# impulse.net
KiCad netlist of a schematic drawn in EAGLE
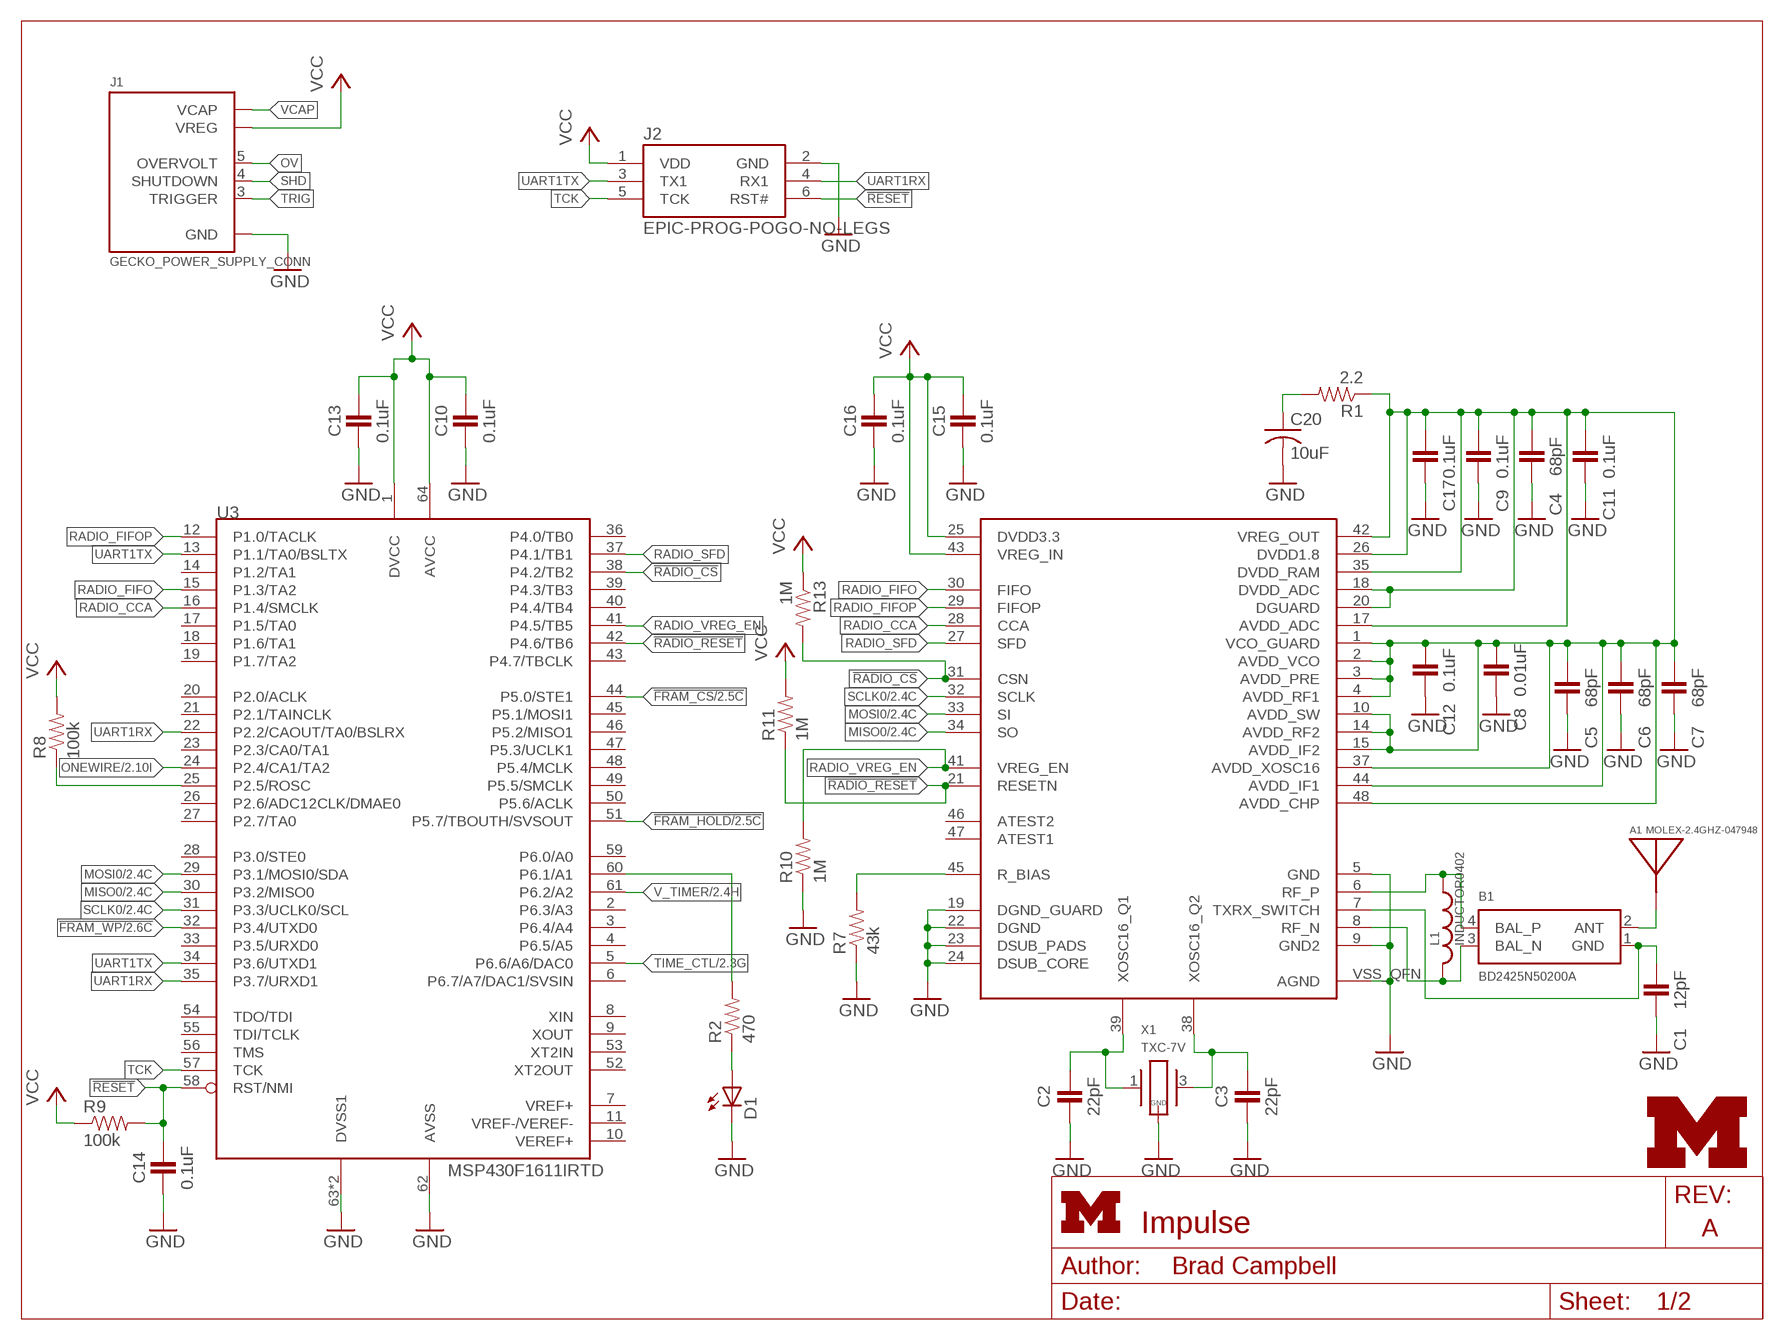
[diagram p0: schematic, sheet 1]
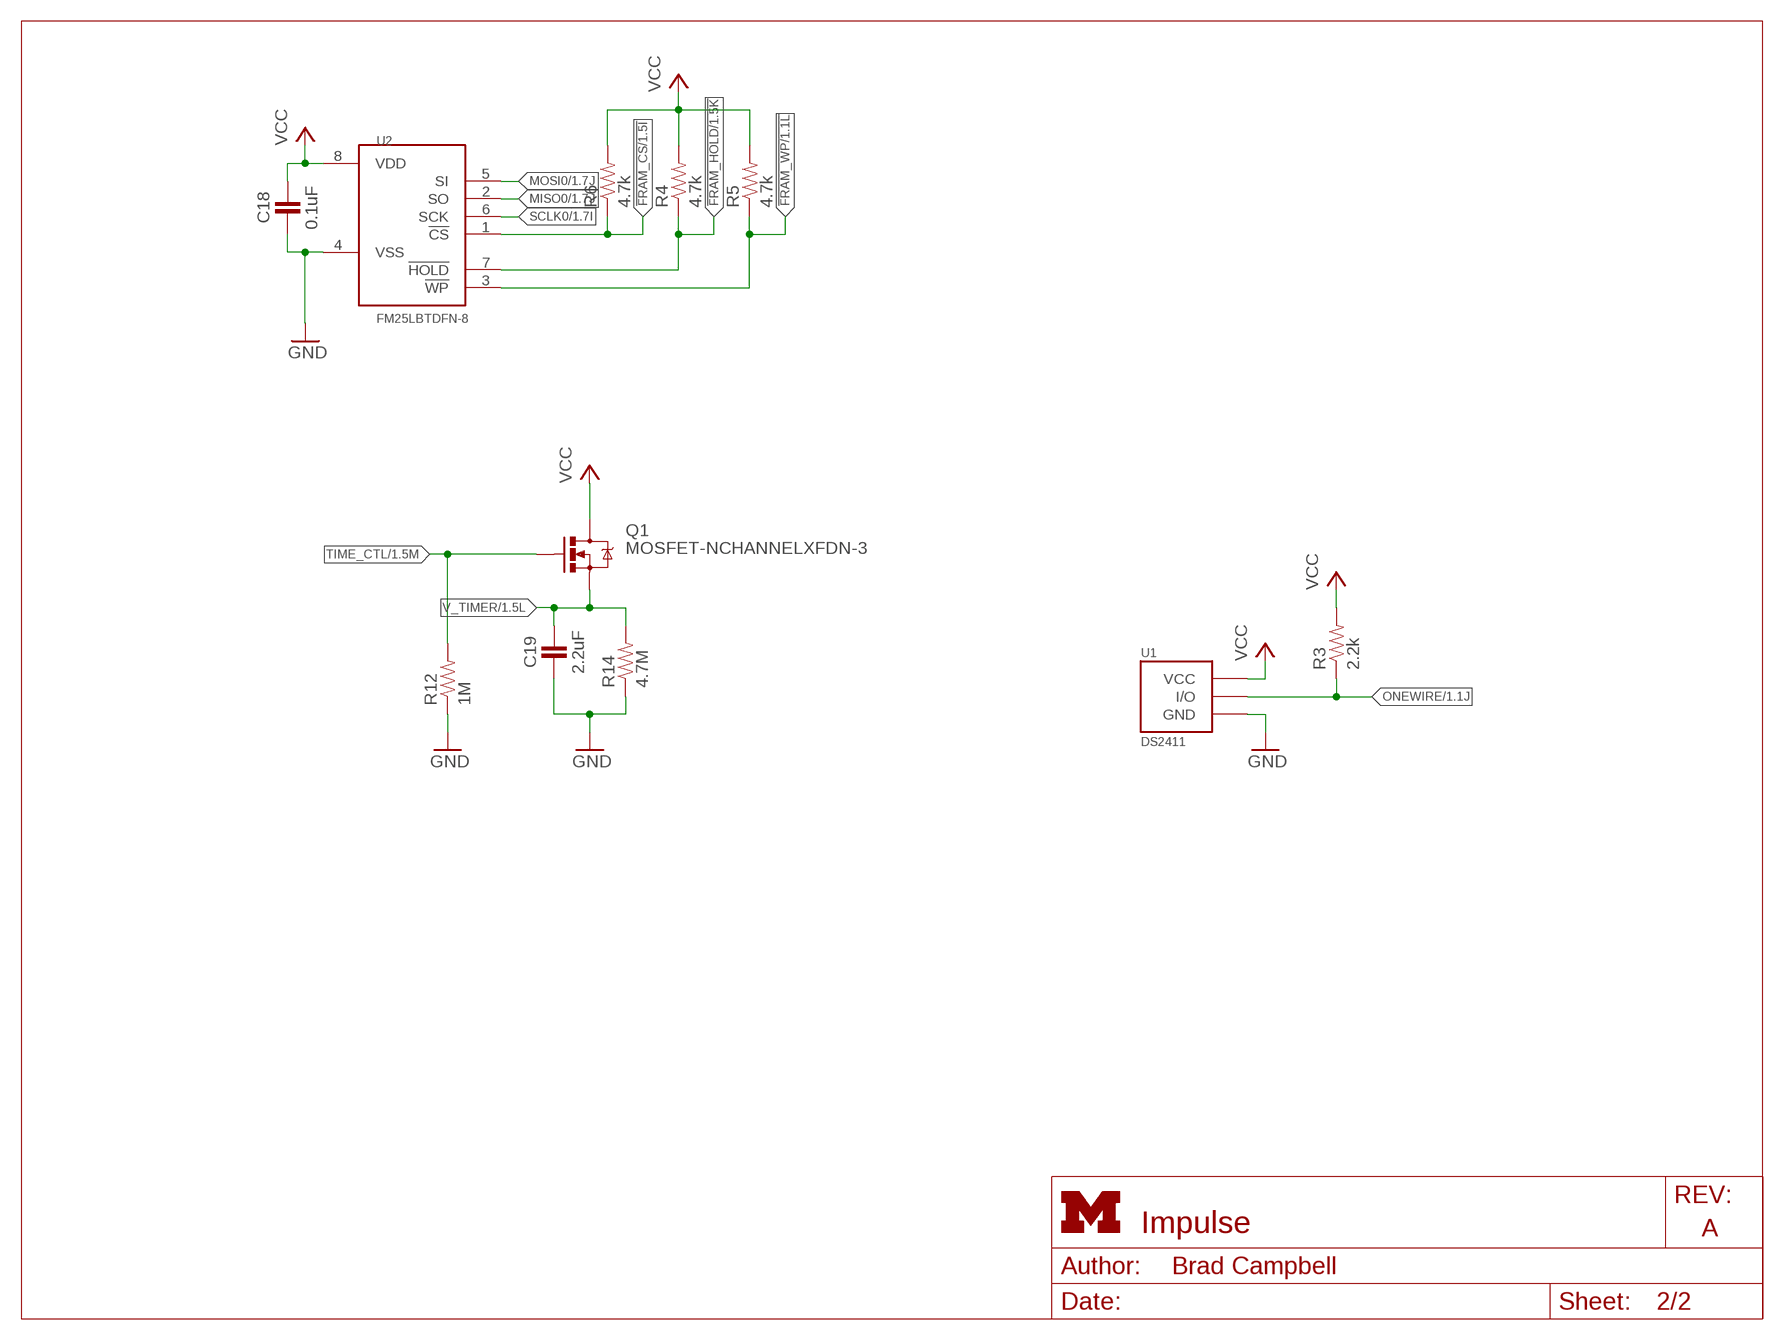
[diagram p1: schematic, sheet 2]

(export (version "E")
  (design (tool "Eeschema 10.0.6"))
  (components
    (comp (ref "A1")
      (value "MOLEX-2.4GHZ-047948")
      (footprint "eagle-import:MOLEX-47948-ANTENNA")
      (libsource (lib "eagle-import") (part "MOLEX-2.4GHZ-047948"))
    )
    (comp (ref "B1")
      (value "BD2425N50200A")
      (footprint "eagle-import:BD2425N50200A")
      (libsource (lib "eagle-import") (part "BD2425N50200A"))
    )
    (comp (ref "C1")
      (value "12pF")
      (footprint "eagle-import:0402_CAP")
      (libsource (lib "eagle-import") (part "CAPACITOR"))
    )
    (comp (ref "C2")
      (value "22pF")
      (footprint "eagle-import:0402_CAP")
      (libsource (lib "eagle-import") (part "CAPACITOR"))
    )
    (comp (ref "C3")
      (value "22pF")
      (footprint "eagle-import:0402_CAP")
      (libsource (lib "eagle-import") (part "CAPACITOR"))
    )
    (comp (ref "C4")
      (value "68pF")
      (footprint "eagle-import:0402_CAP")
      (libsource (lib "eagle-import") (part "CAPACITOR"))
    )
    (comp (ref "C5")
      (value "68pF")
      (footprint "eagle-import:0402_CAP")
      (libsource (lib "eagle-import") (part "CAPACITOR"))
    )
    (comp (ref "C6")
      (value "68pF")
      (footprint "eagle-import:0402_CAP")
      (libsource (lib "eagle-import") (part "CAPACITOR"))
    )
    (comp (ref "C7")
      (value "68pF")
      (footprint "eagle-import:0402_CAP")
      (libsource (lib "eagle-import") (part "CAPACITOR"))
    )
    (comp (ref "C8")
      (value "0.01uF")
      (footprint "eagle-import:0402_CAP")
      (libsource (lib "eagle-import") (part "CAPACITOR"))
    )
    (comp (ref "C9")
      (value "0.1uF")
      (footprint "eagle-import:0402_CAP")
      (libsource (lib "eagle-import") (part "CAPACITOR"))
    )
    (comp (ref "C10")
      (value "0.1uF")
      (footprint "eagle-import:0402_CAP")
      (libsource (lib "eagle-import") (part "CAPACITOR"))
    )
    (comp (ref "C11")
      (value "0.1uF")
      (footprint "eagle-import:0402_CAP")
      (libsource (lib "eagle-import") (part "CAPACITOR"))
    )
    (comp (ref "C12")
      (value "0.1uF")
      (footprint "eagle-import:0402_CAP")
      (libsource (lib "eagle-import") (part "CAPACITOR"))
    )
    (comp (ref "C13")
      (value "0.1uF")
      (footprint "eagle-import:0402_CAP")
      (libsource (lib "eagle-import") (part "CAPACITOR"))
    )
    (comp (ref "C14")
      (value "0.1uF")
      (footprint "eagle-import:0402_CAP")
      (libsource (lib "eagle-import") (part "CAPACITOR"))
    )
    (comp (ref "C15")
      (value "0.1uF")
      (footprint "eagle-import:0402_CAP")
      (libsource (lib "eagle-import") (part "CAPACITOR"))
    )
    (comp (ref "C16")
      (value "0.1uF")
      (footprint "eagle-import:0402_CAP")
      (libsource (lib "eagle-import") (part "CAPACITOR"))
    )
    (comp (ref "C17")
      (value "0.1uF")
      (footprint "eagle-import:0402_CAP")
      (libsource (lib "eagle-import") (part "CAPACITOR"))
    )
    (comp (ref "C20")
      (value "10uF")
      (footprint "eagle-import:C0805")
      (libsource (lib "eagle-import") (part "C-USC0805"))
    )
    (comp (ref "D1")
      (value "LED0603")
      (footprint "eagle-import:LED-0603")
      (libsource (lib "eagle-import") (part "LED0603"))
    )
    (comp (ref "J1")
      (value "GECKO_POWER_SUPPLY_CONN")
      (footprint "eagle-import:HEADER1X6_0.05IN")
      (libsource (lib "eagle-import") (part "GECKO_POWER_SUPPLY_CONN"))
    )
    (comp (ref "J2")
      (value "EPIC-PROG-POGO-NO-LEGS")
      (footprint "eagle-import:TC2030-IDC-NL")
      (libsource (lib "eagle-import") (part "EPIC-PROG-POGO-NO-LEGS"))
    )
    (comp (ref "L1")
      (value "INDUCTOR0402")
      (footprint "eagle-import:0402_CAP")
      (libsource (lib "eagle-import") (part "INDUCTOR0402"))
    )
    (comp (ref "R1")
      (value "2.2")
      (footprint "eagle-import:0402_RES")
      (libsource (lib "eagle-import") (part "RESISTOR"))
    )
    (comp (ref "R2")
      (value "470")
      (footprint "eagle-import:0402_RES")
      (libsource (lib "eagle-import") (part "RESISTOR"))
    )
    (comp (ref "R7")
      (value "43k")
      (footprint "eagle-import:0402_RES")
      (libsource (lib "eagle-import") (part "RESISTOR"))
    )
    (comp (ref "R8")
      (value "100k")
      (footprint "eagle-import:0402_RES")
      (libsource (lib "eagle-import") (part "RESISTOR"))
    )
    (comp (ref "R9")
      (value "100k")
      (footprint "eagle-import:0402_RES")
      (libsource (lib "eagle-import") (part "RESISTOR"))
    )
    (comp (ref "R10")
      (value "1M")
      (footprint "eagle-import:0402_RES")
      (libsource (lib "eagle-import") (part "RESISTOR"))
    )
    (comp (ref "R11")
      (value "1M")
      (footprint "eagle-import:0402_RES")
      (libsource (lib "eagle-import") (part "RESISTOR"))
    )
    (comp (ref "R13")
      (value "1M")
      (footprint "eagle-import:0402_RES")
      (libsource (lib "eagle-import") (part "RESISTOR"))
    )
    (comp (ref "U$1")
      (value "UMICH_SOLID_SMALL")
      (footprint "eagle-import:UMICH_SOLID_75MIL")
      (libsource (lib "eagle-import") (part "UMICH_SOLID_SMALL"))
    )
    (comp (ref "U3")
      (value "MSP430F1611IRTD")
      (footprint "eagle-import:S-PVQFN-N64")
      (libsource (lib "eagle-import") (part "MSP430F1611IRTD"))
    )
    (comp (ref "U4")
      (value "CC2420RGZ")
      (footprint "eagle-import:S-PVQFN-N48")
      (libsource (lib "eagle-import") (part "CC2420RGZ"))
    )
    (comp (ref "X1")
      (value "TXC-7V")
      (footprint "eagle-import:TXC-7V")
      (libsource (lib "eagle-import") (part "TXC-7V"))
    )
    (comp (ref "C18")
      (value "0.1uF")
      (footprint "eagle-import:0402_CAP")
      (libsource (lib "eagle-import") (part "CAPACITOR"))
    )
    (comp (ref "C19")
      (value "2.2uF")
      (footprint "eagle-import:0402_CAP")
      (libsource (lib "eagle-import") (part "CAPACITOR"))
    )
    (comp (ref "Q1")
      (value "MOSFET-NCHANNELXFDN-3")
      (footprint "eagle-import:XFDFN-3")
      (libsource (lib "eagle-import") (part "MOSFET-NCHANNELXFDN-3"))
    )
    (comp (ref "R3")
      (value "2.2k")
      (footprint "eagle-import:0402_RES")
      (libsource (lib "eagle-import") (part "RESISTOR"))
    )
    (comp (ref "R4")
      (value "4.7k")
      (footprint "eagle-import:0402_RES")
      (libsource (lib "eagle-import") (part "RESISTOR"))
    )
    (comp (ref "R5")
      (value "4.7k")
      (footprint "eagle-import:0402_RES")
      (libsource (lib "eagle-import") (part "RESISTOR"))
    )
    (comp (ref "R6")
      (value "4.7k")
      (footprint "eagle-import:0402_RES")
      (libsource (lib "eagle-import") (part "RESISTOR"))
    )
    (comp (ref "R12")
      (value "1M")
      (footprint "eagle-import:0402_RES")
      (libsource (lib "eagle-import") (part "RESISTOR"))
    )
    (comp (ref "R14")
      (value "4.7M")
      (footprint "eagle-import:0402_RES")
      (libsource (lib "eagle-import") (part "RESISTOR"))
    )
    (comp (ref "U1")
      (value "DS2411")
      (footprint "eagle-import:SOT-23")
      (libsource (lib "eagle-import") (part "DS2411"))
    )
    (comp (ref "U2")
      (value "FM25LBTDFN-8")
      (footprint "eagle-import:TDFN-8")
      (libsource (lib "eagle-import") (part "FM25LBTDFN-8"))
    )
  )
  (nets
    (net (code "1") (name "GND") (class "Default")
      (node (ref "C1") (pin "2") (pinfunction "2_2") (pintype "bidirectional"))
      (node (ref "C10") (pin "2") (pinfunction "2_2") (pintype "bidirectional"))
      (node (ref "C11") (pin "2") (pinfunction "2_2") (pintype "bidirectional"))
      (node (ref "C12") (pin "2") (pinfunction "2_2") (pintype "bidirectional"))
      (node (ref "C13") (pin "2") (pinfunction "2_2") (pintype "bidirectional"))
      (node (ref "C14") (pin "2") (pinfunction "2_2") (pintype "bidirectional"))
      (node (ref "C15") (pin "2") (pinfunction "2_2") (pintype "bidirectional"))
      (node (ref "C16") (pin "2") (pinfunction "2_2") (pintype "bidirectional"))
      (node (ref "C17") (pin "2") (pinfunction "2_2") (pintype "bidirectional"))
      (node (ref "C18") (pin "2") (pinfunction "2_2") (pintype "bidirectional"))
      (node (ref "C19") (pin "2") (pinfunction "2_2") (pintype "bidirectional"))
      (node (ref "C2") (pin "2") (pinfunction "2_2") (pintype "bidirectional"))
      (node (ref "C20") (pin "2") (pinfunction "2_2") (pintype "passive"))
      (node (ref "C3") (pin "2") (pinfunction "2_2") (pintype "bidirectional"))
      (node (ref "C4") (pin "2") (pinfunction "2_2") (pintype "bidirectional"))
      (node (ref "C5") (pin "2") (pinfunction "2_2") (pintype "bidirectional"))
      (node (ref "C6") (pin "2") (pinfunction "2_2") (pintype "bidirectional"))
      (node (ref "C7") (pin "2") (pinfunction "2_2") (pintype "bidirectional"))
      (node (ref "C8") (pin "2") (pinfunction "2_2") (pintype "bidirectional"))
      (node (ref "C9") (pin "2") (pinfunction "2_2") (pintype "bidirectional"))
      (node (ref "D1") (pin "C") (pinfunction "C_C") (pintype "passive"))
      (node (ref "J1") (pin "1") (pinfunction "GND_1") (pintype "bidirectional"))
      (node (ref "J2") (pin "2") (pinfunction "GND_2") (pintype "bidirectional"))
      (node (ref "R10") (pin "1") (pinfunction "1_1") (pintype "passive"))
      (node (ref "R12") (pin "1") (pinfunction "1_1") (pintype "passive"))
      (node (ref "R14") (pin "1") (pinfunction "1_1") (pintype "passive"))
      (node (ref "R7") (pin "1") (pinfunction "1_1") (pintype "passive"))
      (node (ref "U1") (pin "3") (pinfunction "GND_3") (pintype "bidirectional"))
      (node (ref "U2") (pin "4") (pinfunction "VSS_4") (pintype "bidirectional"))
      (node (ref "U3") (pin "62") (pinfunction "AVSS_62") (pintype "power_in"))
      (node (ref "U3") (pin "63") (pinfunction "DVSS1_63") (pintype "power_in"))
      (node (ref "U3") (pin "GND") (pinfunction "DVSS1_GND") (pintype "power_in"))
      (node (ref "U4") (pin "19") (pinfunction "DGND_GUARD_19") (pintype "bidirectional"))
      (node (ref "U4") (pin "22") (pinfunction "DGND_22") (pintype "bidirectional"))
      (node (ref "U4") (pin "23") (pinfunction "DSUB_PADS_23") (pintype "bidirectional"))
      (node (ref "U4") (pin "24") (pinfunction "DSUB_CORE_24") (pintype "bidirectional"))
      (node (ref "U4") (pin "5") (pinfunction "GND_5") (pintype "bidirectional"))
      (node (ref "U4") (pin "9") (pinfunction "GND2_9") (pintype "bidirectional"))
      (node (ref "U4") (pin "VSS_QFN") (pinfunction "AGND_VSS_QFN") (pintype "bidirectional"))
      (node (ref "X1") (pin "2") (pinfunction "GND_2") (pintype "bidirectional"))
      (node (ref "X1") (pin "4") (pinfunction "GND_4") (pintype "bidirectional"))
    )
    (net (code "2") (name "MISO0") (class "Default")
      (node (ref "U2") (pin "2") (pinfunction "SO_2") (pintype "bidirectional"))
      (node (ref "U3") (pin "30") (pinfunction "P3.2/MISO0_30") (pintype "bidirectional"))
      (node (ref "U4") (pin "34") (pinfunction "SO_34") (pintype "bidirectional"))
    )
    (net (code "3") (name "MOSI0") (class "Default")
      (node (ref "U2") (pin "5") (pinfunction "SI_5") (pintype "bidirectional"))
      (node (ref "U3") (pin "29") (pinfunction "P3.1/MOSI0/SDA_29") (pintype "bidirectional"))
      (node (ref "U4") (pin "33") (pinfunction "SI_33") (pintype "bidirectional"))
    )
    (net (code "4") (name "Net-(A1-ANTENNA)") (class "Default")
      (node (ref "A1") (pin "1") (pinfunction "ANTENNA_1") (pintype "bidirectional"))
      (node (ref "B1") (pin "2") (pinfunction "ANT_2") (pintype "bidirectional"))
    )
    (net (code "5") (name "Net-(B1-BAL_N)") (class "Default")
      (node (ref "B1") (pin "3") (pinfunction "BAL_N_3") (pintype "bidirectional"))
      (node (ref "L1") (pin "2") (pinfunction "P$2_2") (pintype "bidirectional"))
      (node (ref "U4") (pin "8") (pinfunction "RF_N_8") (pintype "bidirectional"))
    )
    (net (code "6") (name "Net-(B1-BAL_P)") (class "Default")
      (node (ref "B1") (pin "4") (pinfunction "BAL_P_4") (pintype "bidirectional"))
      (node (ref "L1") (pin "1") (pinfunction "1_1") (pintype "bidirectional"))
      (node (ref "U4") (pin "6") (pinfunction "RF_P_6") (pintype "bidirectional"))
    )
    (net (code "7") (name "Net-(B1-GND)") (class "Default")
      (node (ref "B1") (pin "1") (pinfunction "GND_1") (pintype "bidirectional"))
      (node (ref "C1") (pin "1") (pinfunction "1_1") (pintype "bidirectional"))
      (node (ref "U4") (pin "7") (pinfunction "TXRX_SWITCH_7") (pintype "bidirectional"))
    )
    (net (code "8") (name "Net-(C20-Pad1)") (class "Default")
      (node (ref "C20") (pin "1") (pinfunction "1_1") (pintype "passive"))
      (node (ref "R1") (pin "2") (pinfunction "2_2") (pintype "passive"))
    )
    (net (code "9") (name "Net-(D1-PadA)") (class "Default")
      (node (ref "D1") (pin "A") (pinfunction "A_A") (pintype "passive"))
      (node (ref "R2") (pin "1") (pinfunction "1_1") (pintype "passive"))
    )
    (net (code "10") (name "Net-(U3-P2.5{slash}ROSC)") (class "Default")
      (node (ref "R8") (pin "1") (pinfunction "1_1") (pintype "passive"))
      (node (ref "U3") (pin "25") (pinfunction "P2.5/ROSC_25") (pintype "bidirectional"))
    )
    (net (code "11") (name "Net-(U3-P6.1{slash}A1)") (class "Default")
      (node (ref "R2") (pin "2") (pinfunction "2_2") (pintype "passive"))
      (node (ref "U3") (pin "60") (pinfunction "P6.1/A1_60") (pintype "bidirectional"))
    )
    (net (code "12") (name "Net-(U4-AVDD_ADC)") (class "Default")
      (node (ref "C11") (pin "1") (pinfunction "1_1") (pintype "bidirectional"))
      (node (ref "C12") (pin "1") (pinfunction "1_1") (pintype "bidirectional"))
      (node (ref "C17") (pin "1") (pinfunction "1_1") (pintype "bidirectional"))
      (node (ref "C4") (pin "1") (pinfunction "1_1") (pintype "bidirectional"))
      (node (ref "C5") (pin "1") (pinfunction "1_1") (pintype "bidirectional"))
      (node (ref "C6") (pin "1") (pinfunction "1_1") (pintype "bidirectional"))
      (node (ref "C7") (pin "1") (pinfunction "1_1") (pintype "bidirectional"))
      (node (ref "C8") (pin "1") (pinfunction "1_1") (pintype "bidirectional"))
      (node (ref "C9") (pin "1") (pinfunction "1_1") (pintype "bidirectional"))
      (node (ref "R1") (pin "1") (pinfunction "1_1") (pintype "passive"))
      (node (ref "U4") (pin "1") (pinfunction "VCO_GUARD_1") (pintype "bidirectional"))
      (node (ref "U4") (pin "10") (pinfunction "AVDD_SW_10") (pintype "bidirectional"))
      (node (ref "U4") (pin "14") (pinfunction "AVDD_RF2_14") (pintype "bidirectional"))
      (node (ref "U4") (pin "15") (pinfunction "AVDD_IF2_15") (pintype "bidirectional"))
      (node (ref "U4") (pin "17") (pinfunction "AVDD_ADC_17") (pintype "bidirectional"))
      (node (ref "U4") (pin "18") (pinfunction "DVDD_ADC_18") (pintype "bidirectional"))
      (node (ref "U4") (pin "2") (pinfunction "AVDD_VCO_2") (pintype "bidirectional"))
      (node (ref "U4") (pin "20") (pinfunction "DGUARD_20") (pintype "bidirectional"))
      (node (ref "U4") (pin "26") (pinfunction "DVDD1.8_26") (pintype "bidirectional"))
      (node (ref "U4") (pin "3") (pinfunction "AVDD_PRE_3") (pintype "bidirectional"))
      (node (ref "U4") (pin "35") (pinfunction "DVDD_RAM_35") (pintype "bidirectional"))
      (node (ref "U4") (pin "37") (pinfunction "AVDD_XOSC16_37") (pintype "bidirectional"))
      (node (ref "U4") (pin "4") (pinfunction "AVDD_RF1_4") (pintype "bidirectional"))
      (node (ref "U4") (pin "42") (pinfunction "VREG_OUT_42") (pintype "bidirectional"))
      (node (ref "U4") (pin "44") (pinfunction "AVDD_IF1_44") (pintype "bidirectional"))
      (node (ref "U4") (pin "48") (pinfunction "AVDD_CHP_48") (pintype "bidirectional"))
    )
    (net (code "13") (name "Net-(U4-R_BIAS)") (class "Default")
      (node (ref "R7") (pin "2") (pinfunction "2_2") (pintype "passive"))
      (node (ref "U4") (pin "45") (pinfunction "R_BIAS_45") (pintype "bidirectional"))
    )
    (net (code "14") (name "Net-(U4-XOSC16_Q1)") (class "Default")
      (node (ref "C2") (pin "1") (pinfunction "1_1") (pintype "bidirectional"))
      (node (ref "U4") (pin "39") (pinfunction "XOSC16_Q1_39") (pintype "bidirectional"))
      (node (ref "X1") (pin "1") (pinfunction "1_1") (pintype "bidirectional"))
    )
    (net (code "15") (name "Net-(U4-XOSC16_Q2)") (class "Default")
      (node (ref "C3") (pin "1") (pinfunction "1_1") (pintype "bidirectional"))
      (node (ref "U4") (pin "38") (pinfunction "XOSC16_Q2_38") (pintype "bidirectional"))
      (node (ref "X1") (pin "3") (pinfunction "2_3") (pintype "bidirectional"))
    )
    (net (code "16") (name "ONEWIRE") (class "Default")
      (node (ref "R3") (pin "1") (pinfunction "1_1") (pintype "passive"))
      (node (ref "U1") (pin "1") (pinfunction "I/O_1") (pintype "bidirectional"))
      (node (ref "U3") (pin "24") (pinfunction "P2.4/CA1/TA2_24") (pintype "bidirectional"))
    )
    (net (code "17") (name "OV") (class "Default")
      (node (ref "J1") (pin "5") (pinfunction "OVERVOLT_5") (pintype "bidirectional"))
    )
    (net (code "18") (name "RADIO_CCA") (class "Default")
      (node (ref "U3") (pin "16") (pinfunction "P1.4/SMCLK_16") (pintype "bidirectional"))
      (node (ref "U4") (pin "28") (pinfunction "CCA_28") (pintype "bidirectional"))
    )
    (net (code "19") (name "RADIO_FIFO") (class "Default")
      (node (ref "U3") (pin "15") (pinfunction "P1.3/TA2_15") (pintype "bidirectional"))
      (node (ref "U4") (pin "30") (pinfunction "FIFO_30") (pintype "bidirectional"))
    )
    (net (code "20") (name "RADIO_FIFOP") (class "Default")
      (node (ref "U3") (pin "12") (pinfunction "P1.0/TACLK_12") (pintype "bidirectional"))
      (node (ref "U4") (pin "29") (pinfunction "FIFOP_29") (pintype "bidirectional"))
    )
    (net (code "21") (name "RADIO_SFD") (class "Default")
      (node (ref "U3") (pin "37") (pinfunction "P4.1/TB1_37") (pintype "bidirectional"))
      (node (ref "U4") (pin "27") (pinfunction "SFD_27") (pintype "bidirectional"))
    )
    (net (code "22") (name "RADIO_VREG_EN") (class "Default")
      (node (ref "R10") (pin "2") (pinfunction "2_2") (pintype "passive"))
      (node (ref "U3") (pin "41") (pinfunction "P4.5/TB5_41") (pintype "bidirectional"))
      (node (ref "U4") (pin "41") (pinfunction "VREG_EN_41") (pintype "bidirectional"))
    )
    (net (code "23") (name "SCLK0") (class "Default")
      (node (ref "U2") (pin "6") (pinfunction "SCK_6") (pintype "bidirectional"))
      (node (ref "U3") (pin "31") (pinfunction "P3.3/UCLK0/SCL_31") (pintype "bidirectional"))
      (node (ref "U4") (pin "32") (pinfunction "SCLK_32") (pintype "bidirectional"))
    )
    (net (code "24") (name "SHD") (class "Default")
      (node (ref "J1") (pin "4") (pinfunction "SHUTDOWN_4") (pintype "bidirectional"))
    )
    (net (code "25") (name "TCK") (class "Default")
      (node (ref "J2") (pin "5") (pinfunction "TCK_5") (pintype "bidirectional"))
      (node (ref "U3") (pin "57") (pinfunction "TCK_57") (pintype "bidirectional"))
    )
    (net (code "26") (name "TIME_CTL") (class "Default")
      (node (ref "Q1") (pin "G") (pinfunction "G_G") (pintype "passive"))
      (node (ref "R12") (pin "2") (pinfunction "2_2") (pintype "passive"))
      (node (ref "U3") (pin "5") (pinfunction "P6.6/A6/DAC0_5") (pintype "bidirectional"))
    )
    (net (code "27") (name "TRIG") (class "Default")
      (node (ref "J1") (pin "3") (pinfunction "TRIGGER_3") (pintype "bidirectional"))
    )
    (net (code "28") (name "UART1RX") (class "Default")
      (node (ref "J2") (pin "4") (pinfunction "RX1_4") (pintype "bidirectional"))
      (node (ref "U3") (pin "22") (pinfunction "P2.2/CAOUT/TA0/BSLRX_22") (pintype "bidirectional"))
      (node (ref "U3") (pin "35") (pinfunction "P3.7/URXD1_35") (pintype "bidirectional"))
    )
    (net (code "29") (name "UART1TX") (class "Default")
      (node (ref "J2") (pin "3") (pinfunction "TX1_3") (pintype "bidirectional"))
      (node (ref "U3") (pin "13") (pinfunction "P1.1/TA0/BSLTX_13") (pintype "bidirectional"))
      (node (ref "U3") (pin "34") (pinfunction "P3.6/UTXD1_34") (pintype "bidirectional"))
    )
    (net (code "30") (name "VCAP") (class "Default")
      (node (ref "J1") (pin "6") (pinfunction "VCAP_6") (pintype "output"))
    )
    (net (code "31") (name "VCC") (class "Default")
      (node (ref "C10") (pin "1") (pinfunction "1_1") (pintype "bidirectional"))
      (node (ref "C13") (pin "1") (pinfunction "1_1") (pintype "bidirectional"))
      (node (ref "C15") (pin "1") (pinfunction "1_1") (pintype "bidirectional"))
      (node (ref "C16") (pin "1") (pinfunction "1_1") (pintype "bidirectional"))
      (node (ref "C18") (pin "1") (pinfunction "1_1") (pintype "bidirectional"))
      (node (ref "J1") (pin "2") (pinfunction "VREG_2") (pintype "bidirectional"))
      (node (ref "J2") (pin "1") (pinfunction "VDD_1") (pintype "bidirectional"))
      (node (ref "Q1") (pin "D") (pinfunction "D_D") (pintype "passive"))
      (node (ref "R11") (pin "2") (pinfunction "2_2") (pintype "passive"))
      (node (ref "R13") (pin "1") (pinfunction "1_1") (pintype "passive"))
      (node (ref "R3") (pin "2") (pinfunction "2_2") (pintype "passive"))
      (node (ref "R4") (pin "2") (pinfunction "2_2") (pintype "passive"))
      (node (ref "R5") (pin "2") (pinfunction "2_2") (pintype "passive"))
      (node (ref "R6") (pin "2") (pinfunction "2_2") (pintype "passive"))
      (node (ref "R8") (pin "2") (pinfunction "2_2") (pintype "passive"))
      (node (ref "R9") (pin "1") (pinfunction "1_1") (pintype "passive"))
      (node (ref "U1") (pin "2") (pinfunction "VCC_2") (pintype "bidirectional"))
      (node (ref "U2") (pin "8") (pinfunction "VDD_8") (pintype "bidirectional"))
      (node (ref "U3") (pin "1") (pinfunction "DVCC_1") (pintype "power_in"))
      (node (ref "U3") (pin "64") (pinfunction "AVCC_64") (pintype "power_in"))
      (node (ref "U4") (pin "25") (pinfunction "DVDD3.3_25") (pintype "bidirectional"))
      (node (ref "U4") (pin "43") (pinfunction "VREG_IN_43") (pintype "bidirectional"))
    )
    (net (code "32") (name "V_TIMER") (class "Default")
      (node (ref "C19") (pin "1") (pinfunction "1_1") (pintype "bidirectional"))
      (node (ref "Q1") (pin "S") (pinfunction "S_S") (pintype "passive"))
      (node (ref "R14") (pin "2") (pinfunction "2_2") (pintype "passive"))
      (node (ref "U3") (pin "61") (pinfunction "P6.2/A2_61") (pintype "bidirectional"))
    )
    (net (code "33") (name "unconnected-(U3-P1.2{slash}TA1-Pad14)") (class "Default")
      (node (ref "U3") (pin "14") (pinfunction "P1.2/TA1_14") (pintype "bidirectional"))
    )
    (net (code "34") (name "unconnected-(U3-P1.5{slash}TA0-Pad17)") (class "Default")
      (node (ref "U3") (pin "17") (pinfunction "P1.5/TA0_17") (pintype "bidirectional"))
    )
    (net (code "35") (name "unconnected-(U3-P1.6{slash}TA1-Pad18)") (class "Default")
      (node (ref "U3") (pin "18") (pinfunction "P1.6/TA1_18") (pintype "bidirectional"))
    )
    (net (code "36") (name "unconnected-(U3-P1.7{slash}TA2-Pad19)") (class "Default")
      (node (ref "U3") (pin "19") (pinfunction "P1.7/TA2_19") (pintype "bidirectional"))
    )
    (net (code "37") (name "unconnected-(U3-P2.0{slash}ACLK-Pad20)") (class "Default")
      (node (ref "U3") (pin "20") (pinfunction "P2.0/ACLK_20") (pintype "bidirectional"))
    )
    (net (code "38") (name "unconnected-(U3-P2.1{slash}TAINCLK-Pad21)") (class "Default")
      (node (ref "U3") (pin "21") (pinfunction "P2.1/TAINCLK_21") (pintype "bidirectional"))
    )
    (net (code "39") (name "unconnected-(U3-P2.3{slash}CA0{slash}TA1-Pad23)") (class "Default")
      (node (ref "U3") (pin "23") (pinfunction "P2.3/CA0/TA1_23") (pintype "bidirectional"))
    )
    (net (code "40") (name "unconnected-(U3-P2.6{slash}ADC12CLK{slash}DMAE0-Pad26)") (class "Default")
      (node (ref "U3") (pin "26") (pinfunction "P2.6/ADC12CLK/DMAE0_26") (pintype "bidirectional"))
    )
    (net (code "41") (name "unconnected-(U3-P2.7{slash}TA0-Pad27)") (class "Default")
      (node (ref "U3") (pin "27") (pinfunction "P2.7/TA0_27") (pintype "bidirectional"))
    )
    (net (code "42") (name "unconnected-(U3-P3.0{slash}STE0-Pad28)") (class "Default")
      (node (ref "U3") (pin "28") (pinfunction "P3.0/STE0_28") (pintype "bidirectional"))
    )
    (net (code "43") (name "unconnected-(U3-P3.5{slash}URXD0-Pad33)") (class "Default")
      (node (ref "U3") (pin "33") (pinfunction "P3.5/URXD0_33") (pintype "bidirectional"))
    )
    (net (code "44") (name "unconnected-(U3-P4.0{slash}TB0-Pad36)") (class "Default")
      (node (ref "U3") (pin "36") (pinfunction "P4.0/TB0_36") (pintype "bidirectional"))
    )
    (net (code "45") (name "unconnected-(U3-P4.3{slash}TB3-Pad39)") (class "Default")
      (node (ref "U3") (pin "39") (pinfunction "P4.3/TB3_39") (pintype "bidirectional"))
    )
    (net (code "46") (name "unconnected-(U3-P4.4{slash}TB4-Pad40)") (class "Default")
      (node (ref "U3") (pin "40") (pinfunction "P4.4/TB4_40") (pintype "bidirectional"))
    )
    (net (code "47") (name "unconnected-(U3-P4.7{slash}TBCLK-Pad43)") (class "Default")
      (node (ref "U3") (pin "43") (pinfunction "P4.7/TBCLK_43") (pintype "bidirectional"))
    )
    (net (code "48") (name "unconnected-(U3-P5.1{slash}MOSI1-Pad45)") (class "Default")
      (node (ref "U3") (pin "45") (pinfunction "P5.1/MOSI1_45") (pintype "bidirectional"))
    )
    (net (code "49") (name "unconnected-(U3-P5.2{slash}MISO1-Pad46)") (class "Default")
      (node (ref "U3") (pin "46") (pinfunction "P5.2/MISO1_46") (pintype "bidirectional"))
    )
    (net (code "50") (name "unconnected-(U3-P5.3{slash}UCLK1-Pad47)") (class "Default")
      (node (ref "U3") (pin "47") (pinfunction "P5.3/UCLK1_47") (pintype "bidirectional"))
    )
    (net (code "51") (name "unconnected-(U3-P5.4{slash}MCLK-Pad48)") (class "Default")
      (node (ref "U3") (pin "48") (pinfunction "P5.4/MCLK_48") (pintype "bidirectional"))
    )
    (net (code "52") (name "unconnected-(U3-P5.5{slash}SMCLK-Pad49)") (class "Default")
      (node (ref "U3") (pin "49") (pinfunction "P5.5/SMCLK_49") (pintype "bidirectional"))
    )
    (net (code "53") (name "unconnected-(U3-P5.6{slash}ACLK-Pad50)") (class "Default")
      (node (ref "U3") (pin "50") (pinfunction "P5.6/ACLK_50") (pintype "bidirectional"))
    )
    (net (code "54") (name "unconnected-(U3-P6.0{slash}A0-Pad59)") (class "Default")
      (node (ref "U3") (pin "59") (pinfunction "P6.0/A0_59") (pintype "bidirectional"))
    )
    (net (code "55") (name "unconnected-(U3-P6.3{slash}A3-Pad2)") (class "Default")
      (node (ref "U3") (pin "2") (pinfunction "P6.3/A3_2") (pintype "bidirectional"))
    )
    (net (code "56") (name "unconnected-(U3-P6.4{slash}A4-Pad3)") (class "Default")
      (node (ref "U3") (pin "3") (pinfunction "P6.4/A4_3") (pintype "bidirectional"))
    )
    (net (code "57") (name "unconnected-(U3-P6.5{slash}A5-Pad4)") (class "Default")
      (node (ref "U3") (pin "4") (pinfunction "P6.5/A5_4") (pintype "bidirectional"))
    )
    (net (code "58") (name "unconnected-(U3-P6.7{slash}A7{slash}DAC1{slash}SVSIN-Pad6)") (class "Default")
      (node (ref "U3") (pin "6") (pinfunction "P6.7/A7/DAC1/SVSIN_6") (pintype "bidirectional"))
    )
    (net (code "59") (name "unconnected-(U3-TDI{slash}TCLK-Pad55)") (class "Default")
      (node (ref "U3") (pin "55") (pinfunction "TDI/TCLK_55") (pintype "bidirectional"))
    )
    (net (code "60") (name "unconnected-(U3-TDO{slash}TDI-Pad54)") (class "Default")
      (node (ref "U3") (pin "54") (pinfunction "TDO/TDI_54") (pintype "bidirectional"))
    )
    (net (code "61") (name "unconnected-(U3-TMS-Pad56)") (class "Default")
      (node (ref "U3") (pin "56") (pinfunction "TMS_56") (pintype "bidirectional"))
    )
    (net (code "62") (name "unconnected-(U3-VEREF+-Pad10)") (class "Default")
      (node (ref "U3") (pin "10") (pinfunction "VEREF+_10") (pintype "bidirectional"))
    )
    (net (code "63") (name "unconnected-(U3-VREF+-Pad7)") (class "Default")
      (node (ref "U3") (pin "7") (pinfunction "VREF+_7") (pintype "bidirectional"))
    )
    (net (code "64") (name "unconnected-(U3-VREF-{slash}VEREF--Pad11)") (class "Default")
      (node (ref "U3") (pin "11") (pinfunction "VREF-/VEREF-_11") (pintype "bidirectional"))
    )
    (net (code "65") (name "unconnected-(U3-XIN-Pad8)") (class "Default")
      (node (ref "U3") (pin "8") (pinfunction "XIN_8") (pintype "bidirectional"))
    )
    (net (code "66") (name "unconnected-(U3-XOUT-Pad9)") (class "Default")
      (node (ref "U3") (pin "9") (pinfunction "XOUT_9") (pintype "bidirectional"))
    )
    (net (code "67") (name "unconnected-(U3-XT2IN-Pad53)") (class "Default")
      (node (ref "U3") (pin "53") (pinfunction "XT2IN_53") (pintype "bidirectional"))
    )
    (net (code "68") (name "unconnected-(U3-XT2OUT-Pad52)") (class "Default")
      (node (ref "U3") (pin "52") (pinfunction "XT2OUT_52") (pintype "bidirectional"))
    )
    (net (code "69") (name "unconnected-(U4-ATEST1-Pad47)") (class "Default")
      (node (ref "U4") (pin "47") (pinfunction "ATEST1_47") (pintype "bidirectional"))
    )
    (net (code "70") (name "unconnected-(U4-ATEST2-Pad46)") (class "Default")
      (node (ref "U4") (pin "46") (pinfunction "ATEST2_46") (pintype "bidirectional"))
    )
    (net (code "71") (name "~{FRAM_CS}") (class "Default")
      (node (ref "R6") (pin "1") (pinfunction "1_1") (pintype "passive"))
      (node (ref "U2") (pin "1") (pinfunction "~{CS}_1") (pintype "bidirectional"))
      (node (ref "U3") (pin "44") (pinfunction "P5.0/STE1_44") (pintype "bidirectional"))
    )
    (net (code "72") (name "~{FRAM_HOLD}") (class "Default")
      (node (ref "R4") (pin "1") (pinfunction "1_1") (pintype "passive"))
      (node (ref "U2") (pin "7") (pinfunction "~{HOLD}_7") (pintype "bidirectional"))
      (node (ref "U3") (pin "51") (pinfunction "P5.7/TBOUTH/SVSOUT_51") (pintype "bidirectional"))
    )
    (net (code "73") (name "~{FRAM_WP}") (class "Default")
      (node (ref "R5") (pin "1") (pinfunction "1_1") (pintype "passive"))
      (node (ref "U2") (pin "3") (pinfunction "~{WP}_3") (pintype "bidirectional"))
      (node (ref "U3") (pin "32") (pinfunction "P3.4/UTXD0_32") (pintype "bidirectional"))
    )
    (net (code "74") (name "~{RADIO_CS}") (class "Default")
      (node (ref "R13") (pin "2") (pinfunction "2_2") (pintype "passive"))
      (node (ref "U3") (pin "38") (pinfunction "P4.2/TB2_38") (pintype "bidirectional"))
      (node (ref "U4") (pin "31") (pinfunction "CSN_31") (pintype "bidirectional"))
    )
    (net (code "75") (name "~{RADIO_RESET}") (class "Default")
      (node (ref "R11") (pin "1") (pinfunction "1_1") (pintype "passive"))
      (node (ref "U3") (pin "42") (pinfunction "P4.6/TB6_42") (pintype "bidirectional"))
      (node (ref "U4") (pin "21") (pinfunction "RESETN_21") (pintype "bidirectional"))
    )
    (net (code "76") (name "~{RESET}") (class "Default")
      (node (ref "C14") (pin "1") (pinfunction "1_1") (pintype "bidirectional"))
      (node (ref "J2") (pin "6") (pinfunction "RST#_6") (pintype "bidirectional"))
      (node (ref "R9") (pin "2") (pinfunction "2_2") (pintype "passive"))
      (node (ref "U3") (pin "58") (pinfunction "RST/NMI_58") (pintype "bidirectional"))
    )
  )
)
